# relay.net
KiCad netlist of a schematic drawn in EAGLE
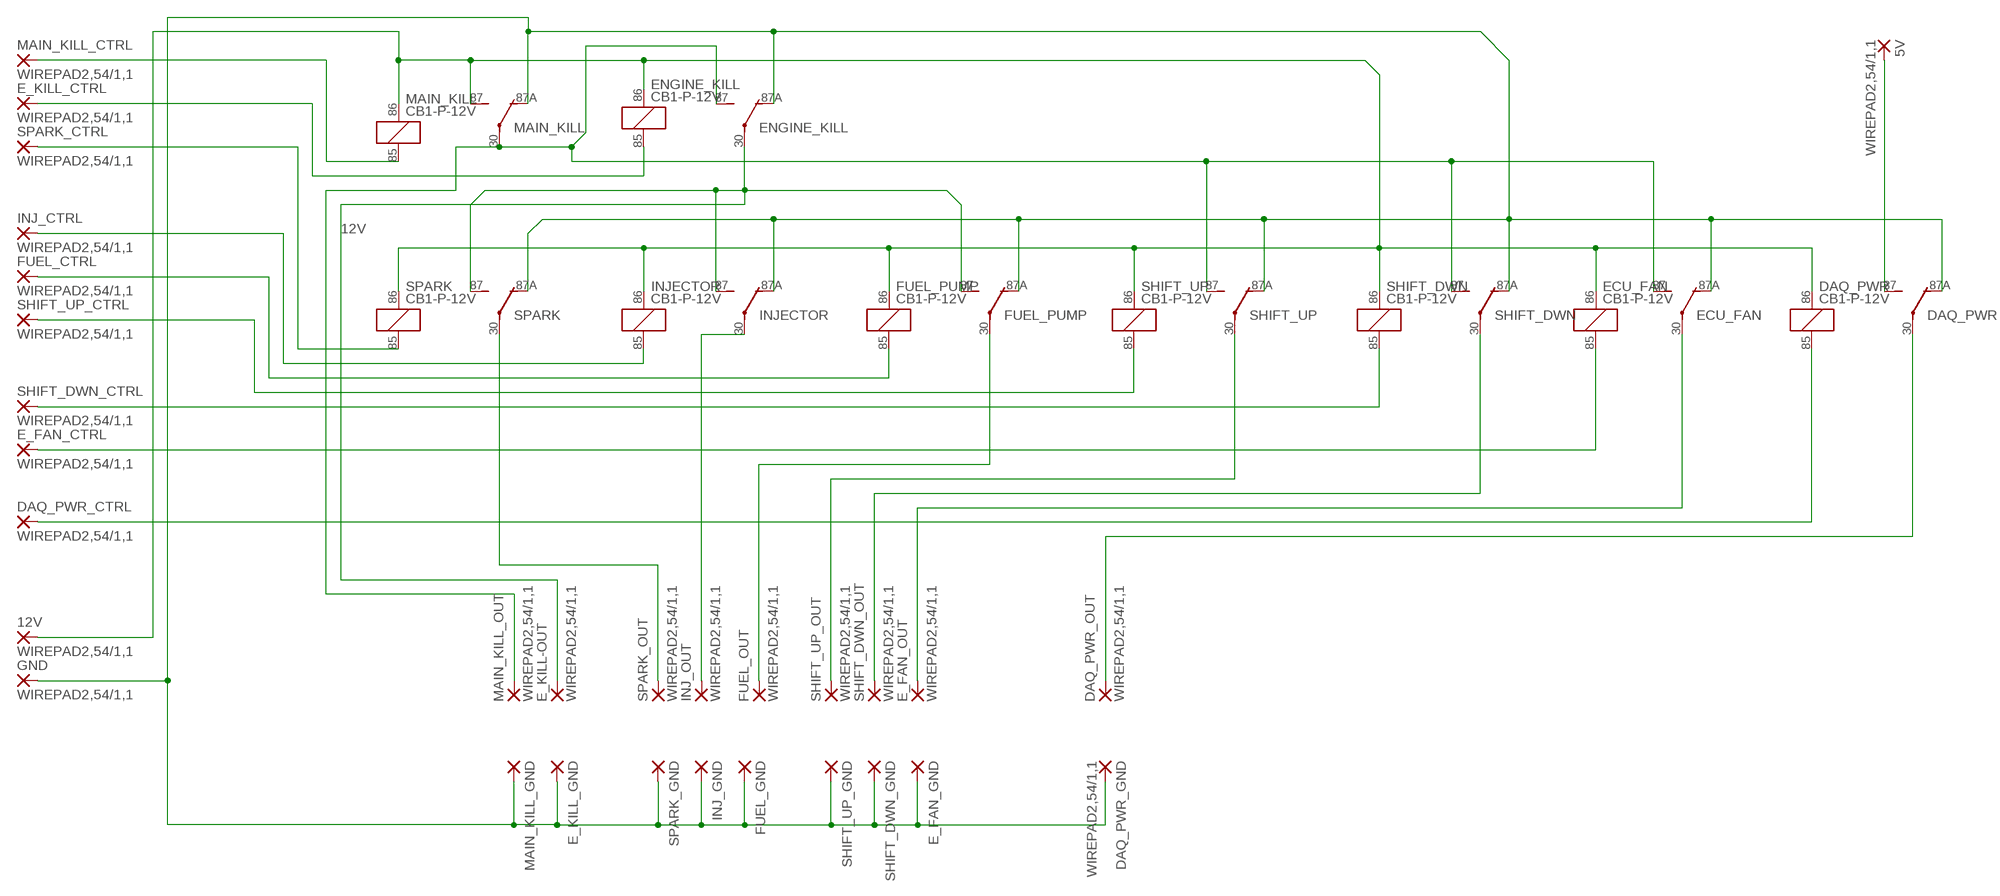
[diagram p0: schematic, sheet 1]

(export (version "E")
  (design (tool "Eeschema 10.0.6"))
  (components
    (comp (ref "5V")
      (value "WIREPAD2,54/1,1")
      (footprint "eagle-import:2,54_1,1")
      (libsource (lib "eagle-import") (part "WIREPAD2,54/1,1"))
    )
    (comp (ref "12V")
      (value "WIREPAD2,54/1,1")
      (footprint "eagle-import:2,54_1,1")
      (libsource (lib "eagle-import") (part "WIREPAD2,54/1,1"))
    )
    (comp (ref "DAQ_PWR")
      (value "CB1-P-12V")
      (footprint "eagle-import:CB1")
      (fields (field (name "MF") "AROMAT/ MATSUSHITA"))
      (libsource (lib "eagle-import") (part "CB1-P-12V"))
    )
    (comp (ref "DAQ_PWR_CTRL")
      (value "WIREPAD2,54/1,1")
      (footprint "eagle-import:2,54_1,1")
      (libsource (lib "eagle-import") (part "WIREPAD2,54/1,1"))
    )
    (comp (ref "DAQ_PWR_GND")
      (value "WIREPAD2,54/1,1")
      (footprint "eagle-import:2,54_1,1")
      (libsource (lib "eagle-import") (part "WIREPAD2,54/1,1"))
    )
    (comp (ref "DAQ_PWR_OUT")
      (value "WIREPAD2,54/1,1")
      (footprint "eagle-import:2,54_1,1")
      (libsource (lib "eagle-import") (part "WIREPAD2,54/1,1"))
    )
    (comp (ref "ECU_FAN")
      (value "CB1-P-12V")
      (footprint "eagle-import:CB1")
      (fields (field (name "MF") "AROMAT/ MATSUSHITA"))
      (libsource (lib "eagle-import") (part "CB1-P-12V"))
    )
    (comp (ref "ENGINE_KILL")
      (value "CB1-P-12V")
      (footprint "eagle-import:CB1")
      (fields (field (name "MF") "AROMAT/ MATSUSHITA"))
      (libsource (lib "eagle-import") (part "CB1-P-12V"))
    )
    (comp (ref "E_FAN_CTRL")
      (value "WIREPAD2,54/1,1")
      (footprint "eagle-import:2,54_1,1")
      (libsource (lib "eagle-import") (part "WIREPAD2,54/1,1"))
    )
    (comp (ref "E_FAN_GND")
      (value "2,54/0,9")
      (footprint "eagle-import:2,54_0,9")
      (libsource (lib "eagle-import") (part "2,54/0,9"))
    )
    (comp (ref "E_FAN_OUT")
      (value "WIREPAD2,54/1,1")
      (footprint "eagle-import:2,54_1,1")
      (libsource (lib "eagle-import") (part "WIREPAD2,54/1,1"))
    )
    (comp (ref "E_KILL-OUT")
      (value "WIREPAD2,54/1,1")
      (footprint "eagle-import:2,54_1,1")
      (libsource (lib "eagle-import") (part "WIREPAD2,54/1,1"))
    )
    (comp (ref "E_KILL_CTRL")
      (value "WIREPAD2,54/1,1")
      (footprint "eagle-import:2,54_1,1")
      (libsource (lib "eagle-import") (part "WIREPAD2,54/1,1"))
    )
    (comp (ref "E_KILL_GND")
      (value "2,54/0,9")
      (footprint "eagle-import:2,54_0,9")
      (libsource (lib "eagle-import") (part "2,54/0,9"))
    )
    (comp (ref "FUEL_CTRL")
      (value "WIREPAD2,54/1,1")
      (footprint "eagle-import:2,54_1,1")
      (libsource (lib "eagle-import") (part "WIREPAD2,54/1,1"))
    )
    (comp (ref "FUEL_GND")
      (value "2,54/0,9")
      (footprint "eagle-import:2,54_0,9")
      (libsource (lib "eagle-import") (part "2,54/0,9"))
    )
    (comp (ref "FUEL_OUT")
      (value "WIREPAD2,54/1,1")
      (footprint "eagle-import:2,54_1,1")
      (libsource (lib "eagle-import") (part "WIREPAD2,54/1,1"))
    )
    (comp (ref "FUEL_PUMP")
      (value "CB1-P-12V")
      (footprint "eagle-import:CB1")
      (fields (field (name "MF") "AROMAT/ MATSUSHITA"))
      (libsource (lib "eagle-import") (part "CB1-P-12V"))
    )
    (comp (ref "GND")
      (value "WIREPAD2,54/1,1")
      (footprint "eagle-import:2,54_1,1")
      (libsource (lib "eagle-import") (part "WIREPAD2,54/1,1"))
    )
    (comp (ref "INJECTOR")
      (value "CB1-P-12V")
      (footprint "eagle-import:CB1")
      (fields (field (name "MF") "AROMAT/ MATSUSHITA"))
      (libsource (lib "eagle-import") (part "CB1-P-12V"))
    )
    (comp (ref "INJ_CTRL")
      (value "WIREPAD2,54/1,1")
      (footprint "eagle-import:2,54_1,1")
      (libsource (lib "eagle-import") (part "WIREPAD2,54/1,1"))
    )
    (comp (ref "INJ_GND")
      (value "2,54/0,9")
      (footprint "eagle-import:2,54_0,9")
      (libsource (lib "eagle-import") (part "2,54/0,9"))
    )
    (comp (ref "INJ_OUT")
      (value "WIREPAD2,54/1,1")
      (footprint "eagle-import:2,54_1,1")
      (libsource (lib "eagle-import") (part "WIREPAD2,54/1,1"))
    )
    (comp (ref "MAIN_KILL")
      (value "CB1-P-12V")
      (footprint "eagle-import:CB1")
      (fields (field (name "MF") "AROMAT/ MATSUSHITA"))
      (libsource (lib "eagle-import") (part "CB1-P-12V"))
    )
    (comp (ref "MAIN_KILL_CTRL")
      (value "WIREPAD2,54/1,1")
      (footprint "eagle-import:2,54_1,1")
      (libsource (lib "eagle-import") (part "WIREPAD2,54/1,1"))
    )
    (comp (ref "MAIN_KILL_GND")
      (value "2,54/0,9")
      (footprint "eagle-import:2,54_0,9")
      (libsource (lib "eagle-import") (part "2,54/0,9"))
    )
    (comp (ref "MAIN_KILL_OUT")
      (value "WIREPAD2,54/1,1")
      (footprint "eagle-import:2,54_1,1")
      (libsource (lib "eagle-import") (part "WIREPAD2,54/1,1"))
    )
    (comp (ref "SHIFT_DWN")
      (value "CB1-P-12V")
      (footprint "eagle-import:CB1")
      (fields (field (name "MF") "AROMAT/ MATSUSHITA"))
      (libsource (lib "eagle-import") (part "CB1-P-12V"))
    )
    (comp (ref "SHIFT_DWN_CTRL")
      (value "WIREPAD2,54/1,1")
      (footprint "eagle-import:2,54_1,1")
      (libsource (lib "eagle-import") (part "WIREPAD2,54/1,1"))
    )
    (comp (ref "SHIFT_DWN_GND")
      (value "2,54/0,9")
      (footprint "eagle-import:2,54_0,9")
      (libsource (lib "eagle-import") (part "2,54/0,9"))
    )
    (comp (ref "SHIFT_DWN_OUT")
      (value "WIREPAD2,54/1,1")
      (footprint "eagle-import:2,54_1,1")
      (libsource (lib "eagle-import") (part "WIREPAD2,54/1,1"))
    )
    (comp (ref "SHIFT_UP")
      (value "CB1-P-12V")
      (footprint "eagle-import:CB1")
      (fields (field (name "MF") "AROMAT/ MATSUSHITA"))
      (libsource (lib "eagle-import") (part "CB1-P-12V"))
    )
    (comp (ref "SHIFT_UP_CTRL")
      (value "WIREPAD2,54/1,1")
      (footprint "eagle-import:2,54_1,1")
      (libsource (lib "eagle-import") (part "WIREPAD2,54/1,1"))
    )
    (comp (ref "SHIFT_UP_GND")
      (value "2,54/0,9")
      (footprint "eagle-import:2,54_0,9")
      (libsource (lib "eagle-import") (part "2,54/0,9"))
    )
    (comp (ref "SHIFT_UP_OUT")
      (value "WIREPAD2,54/1,1")
      (footprint "eagle-import:2,54_1,1")
      (libsource (lib "eagle-import") (part "WIREPAD2,54/1,1"))
    )
    (comp (ref "SPARK")
      (value "CB1-P-12V")
      (footprint "eagle-import:CB1")
      (fields (field (name "MF") "AROMAT/ MATSUSHITA"))
      (libsource (lib "eagle-import") (part "CB1-P-12V"))
    )
    (comp (ref "SPARK_CTRL")
      (value "WIREPAD2,54/1,1")
      (footprint "eagle-import:2,54_1,1")
      (libsource (lib "eagle-import") (part "WIREPAD2,54/1,1"))
    )
    (comp (ref "SPARK_GND")
      (value "2,54/0,9")
      (footprint "eagle-import:2,54_0,9")
      (libsource (lib "eagle-import") (part "2,54/0,9"))
    )
    (comp (ref "SPARK_OUT")
      (value "WIREPAD2,54/1,1")
      (footprint "eagle-import:2,54_1,1")
      (libsource (lib "eagle-import") (part "WIREPAD2,54/1,1"))
    )
  )
  (nets
    (net (code "1") (name "/12V") (class "Default")
      (node (ref "12V") (pin "1") (pinfunction "P_1") (pintype "passive"))
      (node (ref "DAQ_PWR") (pin "86") (pinfunction "1_86") (pintype "passive"))
      (node (ref "ECU_FAN") (pin "86") (pinfunction "1_86") (pintype "passive"))
      (node (ref "ENGINE_KILL") (pin "86") (pinfunction "1_86") (pintype "passive"))
      (node (ref "FUEL_PUMP") (pin "86") (pinfunction "1_86") (pintype "passive"))
      (node (ref "INJECTOR") (pin "86") (pinfunction "1_86") (pintype "passive"))
      (node (ref "MAIN_KILL") (pin "86") (pinfunction "1_86") (pintype "passive"))
      (node (ref "MAIN_KILL") (pin "87") (pinfunction "S_87") (pintype "passive"))
      (node (ref "SHIFT_DWN") (pin "86") (pinfunction "1_86") (pintype "passive"))
      (node (ref "SHIFT_UP") (pin "86") (pinfunction "1_86") (pintype "passive"))
      (node (ref "SPARK") (pin "86") (pinfunction "1_86") (pintype "passive"))
    )
    (net (code "2") (name "Net-(5V-P)") (class "Default")
      (node (ref "5V") (pin "1") (pinfunction "P_1") (pintype "passive"))
      (node (ref "DAQ_PWR") (pin "87") (pinfunction "S_87") (pintype "passive"))
    )
    (net (code "3") (name "Net-(DAQ_PWRA-2)") (class "Default")
      (node (ref "DAQ_PWR") (pin "85") (pinfunction "2_85") (pintype "passive"))
      (node (ref "DAQ_PWR_CTRL") (pin "1") (pinfunction "P_1") (pintype "passive"))
    )
    (net (code "4") (name "Net-(DAQ_PWRB-O)") (class "Default")
      (node (ref "DAQ_PWR") (pin "87A") (pinfunction "O_87A") (pintype "passive"))
      (node (ref "DAQ_PWR_GND") (pin "1") (pinfunction "P_1") (pintype "passive"))
      (node (ref "ECU_FAN") (pin "87A") (pinfunction "O_87A") (pintype "passive"))
      (node (ref "ENGINE_KILL") (pin "87A") (pinfunction "O_87A") (pintype "passive"))
      (node (ref "E_FAN_GND") (pin "1") (pinfunction "P_1") (pintype "passive"))
      (node (ref "E_KILL_GND") (pin "1") (pinfunction "P_1") (pintype "passive"))
      (node (ref "FUEL_GND") (pin "1") (pinfunction "P_1") (pintype "passive"))
      (node (ref "FUEL_PUMP") (pin "87A") (pinfunction "O_87A") (pintype "passive"))
      (node (ref "GND") (pin "1") (pinfunction "P_1") (pintype "passive"))
      (node (ref "INJECTOR") (pin "87A") (pinfunction "O_87A") (pintype "passive"))
      (node (ref "INJ_GND") (pin "1") (pinfunction "P_1") (pintype "passive"))
      (node (ref "MAIN_KILL") (pin "87A") (pinfunction "O_87A") (pintype "passive"))
      (node (ref "MAIN_KILL_GND") (pin "1") (pinfunction "P_1") (pintype "passive"))
      (node (ref "SHIFT_DWN") (pin "87A") (pinfunction "O_87A") (pintype "passive"))
      (node (ref "SHIFT_DWN_GND") (pin "1") (pinfunction "P_1") (pintype "passive"))
      (node (ref "SHIFT_UP") (pin "87A") (pinfunction "O_87A") (pintype "passive"))
      (node (ref "SHIFT_UP_GND") (pin "1") (pinfunction "P_1") (pintype "passive"))
      (node (ref "SPARK") (pin "87A") (pinfunction "O_87A") (pintype "passive"))
      (node (ref "SPARK_GND") (pin "1") (pinfunction "P_1") (pintype "passive"))
    )
    (net (code "5") (name "Net-(DAQ_PWRB-P)") (class "Default")
      (node (ref "DAQ_PWR") (pin "30") (pinfunction "P_30") (pintype "passive"))
      (node (ref "DAQ_PWR_OUT") (pin "1") (pinfunction "P_1") (pintype "passive"))
    )
    (net (code "6") (name "Net-(ECU_FANA-2)") (class "Default")
      (node (ref "ECU_FAN") (pin "85") (pinfunction "2_85") (pintype "passive"))
      (node (ref "E_FAN_CTRL") (pin "1") (pinfunction "P_1") (pintype "passive"))
    )
    (net (code "7") (name "Net-(ECU_FANB-P)") (class "Default")
      (node (ref "ECU_FAN") (pin "30") (pinfunction "P_30") (pintype "passive"))
      (node (ref "E_FAN_OUT") (pin "1") (pinfunction "P_1") (pintype "passive"))
    )
    (net (code "8") (name "Net-(ECU_FANB-S)") (class "Default")
      (node (ref "ECU_FAN") (pin "87") (pinfunction "S_87") (pintype "passive"))
      (node (ref "ENGINE_KILL") (pin "87") (pinfunction "S_87") (pintype "passive"))
      (node (ref "MAIN_KILL") (pin "30") (pinfunction "P_30") (pintype "passive"))
      (node (ref "MAIN_KILL_OUT") (pin "1") (pinfunction "P_1") (pintype "passive"))
      (node (ref "SHIFT_DWN") (pin "87") (pinfunction "S_87") (pintype "passive"))
      (node (ref "SHIFT_UP") (pin "87") (pinfunction "S_87") (pintype "passive"))
    )
    (net (code "9") (name "Net-(ENGINE_KILLA-2)") (class "Default")
      (node (ref "ENGINE_KILL") (pin "85") (pinfunction "2_85") (pintype "passive"))
      (node (ref "E_KILL_CTRL") (pin "1") (pinfunction "P_1") (pintype "passive"))
    )
    (net (code "10") (name "Net-(ENGINE_KILLB-P)") (class "Default")
      (node (ref "ENGINE_KILL") (pin "30") (pinfunction "P_30") (pintype "passive"))
      (node (ref "E_KILL-OUT") (pin "1") (pinfunction "P_1") (pintype "passive"))
      (node (ref "FUEL_PUMP") (pin "87") (pinfunction "S_87") (pintype "passive"))
      (node (ref "INJECTOR") (pin "87") (pinfunction "S_87") (pintype "passive"))
      (node (ref "SPARK") (pin "87") (pinfunction "S_87") (pintype "passive"))
    )
    (net (code "11") (name "Net-(FUEL_CTRL-P)") (class "Default")
      (node (ref "FUEL_CTRL") (pin "1") (pinfunction "P_1") (pintype "passive"))
      (node (ref "FUEL_PUMP") (pin "85") (pinfunction "2_85") (pintype "passive"))
    )
    (net (code "12") (name "Net-(FUEL_OUT-P)") (class "Default")
      (node (ref "FUEL_OUT") (pin "1") (pinfunction "P_1") (pintype "passive"))
      (node (ref "FUEL_PUMP") (pin "30") (pinfunction "P_30") (pintype "passive"))
    )
    (net (code "13") (name "Net-(INJECTORA-2)") (class "Default")
      (node (ref "INJECTOR") (pin "85") (pinfunction "2_85") (pintype "passive"))
      (node (ref "INJ_CTRL") (pin "1") (pinfunction "P_1") (pintype "passive"))
    )
    (net (code "14") (name "Net-(INJECTORB-P)") (class "Default")
      (node (ref "INJECTOR") (pin "30") (pinfunction "P_30") (pintype "passive"))
      (node (ref "INJ_OUT") (pin "1") (pinfunction "P_1") (pintype "passive"))
    )
    (net (code "15") (name "Net-(MAIN_KILLA-2)") (class "Default")
      (node (ref "MAIN_KILL") (pin "85") (pinfunction "2_85") (pintype "passive"))
      (node (ref "MAIN_KILL_CTRL") (pin "1") (pinfunction "P_1") (pintype "passive"))
    )
    (net (code "16") (name "Net-(SHIFT_DWNA-2)") (class "Default")
      (node (ref "SHIFT_DWN") (pin "85") (pinfunction "2_85") (pintype "passive"))
      (node (ref "SHIFT_DWN_CTRL") (pin "1") (pinfunction "P_1") (pintype "passive"))
    )
    (net (code "17") (name "Net-(SHIFT_DWNB-P)") (class "Default")
      (node (ref "SHIFT_DWN") (pin "30") (pinfunction "P_30") (pintype "passive"))
      (node (ref "SHIFT_DWN_OUT") (pin "1") (pinfunction "P_1") (pintype "passive"))
    )
    (net (code "18") (name "Net-(SHIFT_UPA-2)") (class "Default")
      (node (ref "SHIFT_UP") (pin "85") (pinfunction "2_85") (pintype "passive"))
      (node (ref "SHIFT_UP_CTRL") (pin "1") (pinfunction "P_1") (pintype "passive"))
    )
    (net (code "19") (name "Net-(SHIFT_UPB-P)") (class "Default")
      (node (ref "SHIFT_UP") (pin "30") (pinfunction "P_30") (pintype "passive"))
      (node (ref "SHIFT_UP_OUT") (pin "1") (pinfunction "P_1") (pintype "passive"))
    )
    (net (code "20") (name "Net-(SPARKA-2)") (class "Default")
      (node (ref "SPARK") (pin "85") (pinfunction "2_85") (pintype "passive"))
      (node (ref "SPARK_CTRL") (pin "1") (pinfunction "P_1") (pintype "passive"))
    )
    (net (code "21") (name "Net-(SPARKB-P)") (class "Default")
      (node (ref "SPARK") (pin "30") (pinfunction "P_30") (pintype "passive"))
      (node (ref "SPARK_OUT") (pin "1") (pinfunction "P_1") (pintype "passive"))
    )
  )
)
